# 3_bootleg-alps-mcu.net
KiCad netlist of a schematic drawn in Altium Designer
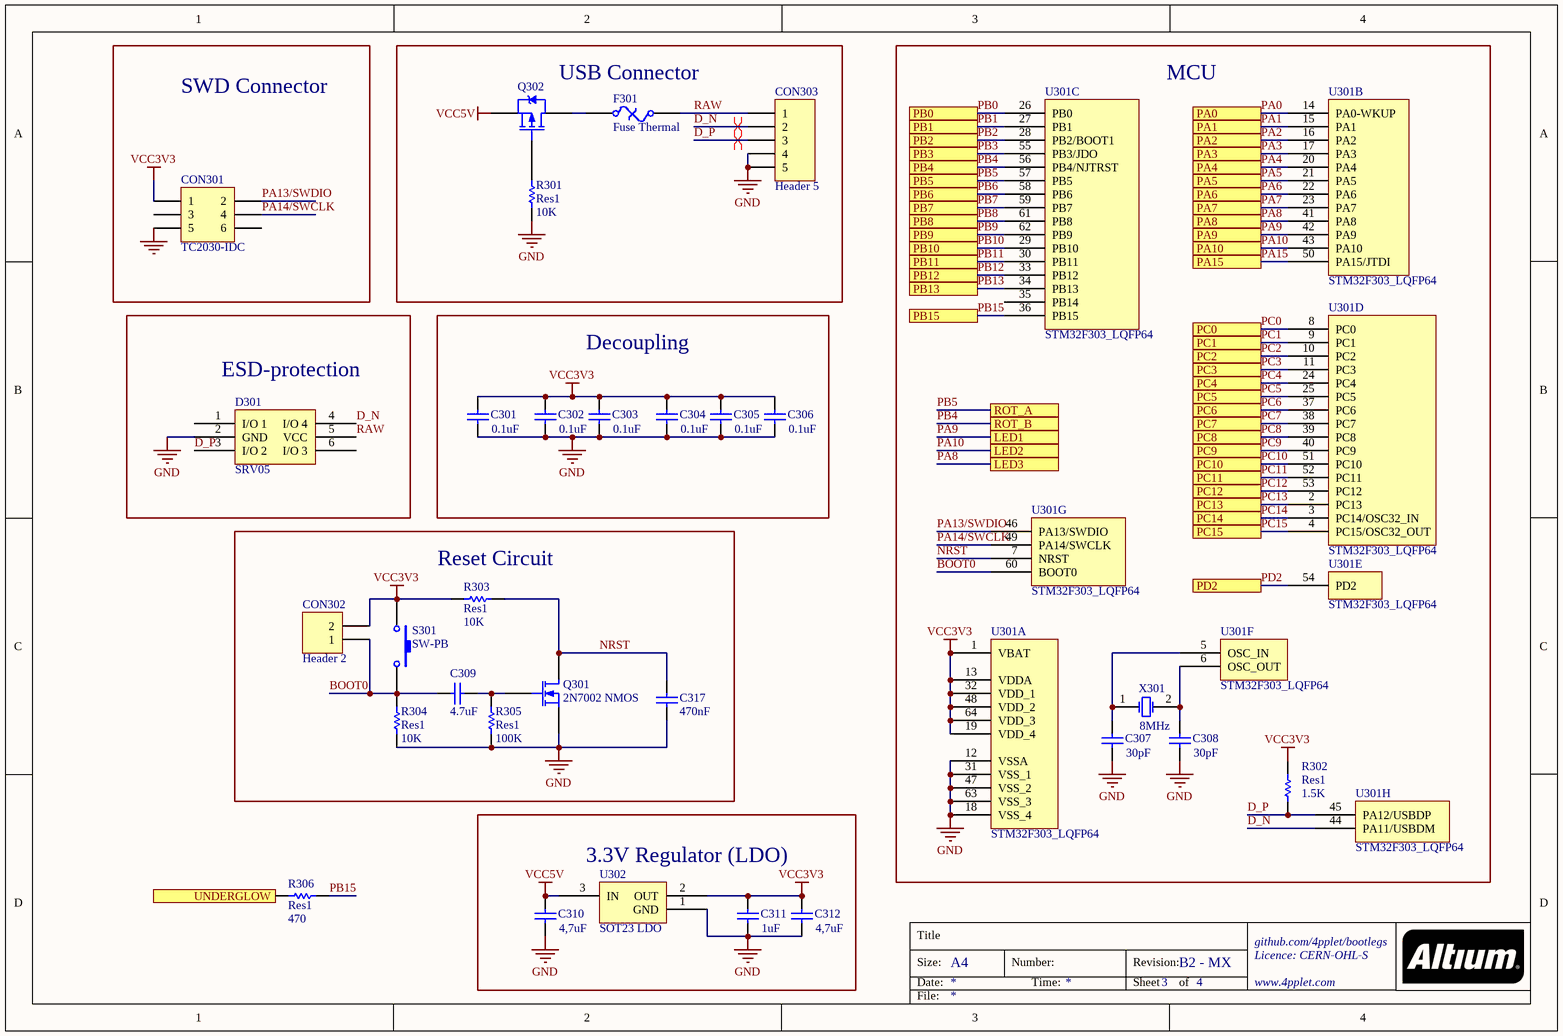
[diagram p0: 3_bootleg-alps-mcu.SchDoc]

(export (version "E")
  (design (tool "Eeschema 10.0.6"))
  (components
    (comp (ref "C301")
      (value "0.1uF")
      (footprint "C0603[1608]")
      (description "Capacitor")
      (fields (field (name "MFG") "KEMET") (field (name "LCSC PART #") "C14663"))
      (libsource (lib "Miscellaneous Devices") (part "Cap"))
    )
    (comp (ref "C302")
      (value "0.1uF")
      (footprint "C0603[1608]")
      (description "Capacitor")
      (fields (field (name "MFG") "KEMET") (field (name "LCSC PART #") "C14663"))
      (libsource (lib "Miscellaneous Devices") (part "Cap"))
    )
    (comp (ref "C303")
      (value "0.1uF")
      (footprint "C0603[1608]")
      (description "Capacitor")
      (fields (field (name "MFG") "KEMET") (field (name "LCSC PART #") "C14663"))
      (libsource (lib "Miscellaneous Devices") (part "Cap"))
    )
    (comp (ref "C304")
      (value "0.1uF")
      (footprint "C0603[1608]")
      (description "Capacitor")
      (fields (field (name "MFG") "KEMET") (field (name "LCSC PART #") "C14663"))
      (libsource (lib "Miscellaneous Devices") (part "Cap"))
    )
    (comp (ref "C305")
      (value "0.1uF")
      (footprint "C0603[1608]")
      (description "Capacitor")
      (fields (field (name "MFG") "KEMET") (field (name "LCSC PART #") "C14663"))
      (libsource (lib "Miscellaneous Devices") (part "Cap"))
    )
    (comp (ref "C306")
      (value "0.1uF")
      (footprint "C0603[1608]")
      (description "Capacitor")
      (fields (field (name "MFG") "KEMET") (field (name "LCSC PART #") "C14663"))
      (libsource (lib "Miscellaneous Devices") (part "Cap"))
    )
    (comp (ref "C307")
      (value "30pF")
      (footprint "C0603[1608]")
      (description "Capacitor")
      (fields (field (name "LCSC PART #") "C22397") (field (name "MRF.PART") "CL10C300JB8NNNC"))
      (libsource (lib "Miscellaneous Devices") (part "Cap"))
    )
    (comp (ref "C308")
      (value "30pF")
      (footprint "C0603[1608]")
      (description "Capacitor")
      (fields (field (name "LCSC PART #") "C22397") (field (name "MRF.PART") "CL10C300JB8NNNC"))
      (libsource (lib "Miscellaneous Devices") (part "Cap"))
    )
    (comp (ref "C309")
      (value "4.7uF")
      (footprint "C0603[1608]")
      (description "Capacitor")
      (fields (field (name "LCSC PART #") "C19666"))
      (libsource (lib "Miscellaneous Devices") (part "Cap"))
    )
    (comp (ref "C310")
      (value "4,7uF")
      (footprint "C0603[1608]")
      (description "Capacitor")
      (fields (field (name "LCSC PART #") "C19666"))
      (libsource (lib "Miscellaneous Devices") (part "Cap"))
    )
    (comp (ref "C311")
      (value "1uF")
      (footprint "C0603[1608]")
      (description "Capacitor")
      (fields (field (name "MFG") "KEMET") (field (name "LCSC PART #") "C15849"))
      (libsource (lib "Miscellaneous Devices") (part "Cap"))
    )
    (comp (ref "C312")
      (value "4,7uF")
      (footprint "C0603[1608]")
      (description "Capacitor")
      (fields (field (name "LCSC PART #") "C19666"))
      (libsource (lib "Miscellaneous Devices") (part "Cap"))
    )
    (comp (ref "C317")
      (value "470nF")
      (footprint "C0603[1608]")
      (description "Capacitor")
      (fields (field (name "MFG") "KEMET") (field (name "LCSC PART #") "C14663"))
      (libsource (lib "Miscellaneous Devices") (part "Cap"))
    )
    (comp (ref "CON301")
      (value "TC2030-IDC")
      (footprint "TC2030-IDC-NL")
      (description "Header, 3-Pin, Dual row")
      (libsource (lib "Miscellaneous Connectors") (part "Header 3X2"))
    )
    (comp (ref "CON302")
      (value "Header 2")
      (footprint "HDR1X2")
      (description "Header, 2-Pin")
      (libsource (lib "Miscellaneous Connectors") (part "Header 2"))
    )
    (comp (ref "CON303")
      (value "Header 5")
      (footprint "JST SM04B-SRSS-TB")
      (description "JST for USB daughter board")
      (fields (field (name "MFG") "JST Sales America Inc.") (field (name "LCSC PART #") "C160404"))
      (libsource (lib "Miscellaneous Connectors") (part "Header 5"))
    )
    (comp (ref "D301")
      (value "SRV05")
      (footprint "SOT-23-6")
      (fields (field (name "LCSC PART #") "C85364") (field (name "MRF.PART") "SRV05-4-P-T7"))
      (libsource (lib "Keebs") (part "SRV05"))
    )
    (comp (ref "F301")
      (value "Fuse Thermal")
      (footprint "C1206[3216]")
      (description "Thermal Fuse")
      (fields (field (name "MFG") "Bel Fuse Inc.") (field (name "LCSC PART #") "C135338"))
      (libsource (lib "Miscellaneous Devices") (part "Fuse Thermal"))
    )
    (comp (ref "Q301")
      (value "2N7002 NMOS")
      (footprint "SOT-23-3")
      (description "N-Channel MOSFET")
      (fields (field (name "LCSC PART #") "C8545") (field (name "MRF.PART") "2N7002"))
      (libsource (lib "Miscellaneous Devices") (part "MOSFET-N"))
    )
    (comp (ref "Q302")
      (value "PMOS-2")
      (footprint "SOT-23-3")
      (description "P-Channel Power MOSFET")
      (fields (field (name "LCSC PART #") "C10487") (field (name "MRF.PART") "SI2301CDS-T1-GE3"))
      (libsource (lib "Miscellaneous Devices") (part "PMOS-2"))
    )
    (comp (ref "R301")
      (value "Res1")
      (footprint "R0603[1608]")
      (description "Resistor")
      (fields
        (field (name "ALTIUM_VALUE") "10K")
        (field (name "MFG") "Panasonic Electronic Components")
        (field (name "LCSC PART #") "C25804")
      )
      (libsource (lib "Miscellaneous Devices") (part "Res1"))
    )
    (comp (ref "R302")
      (value "Res1")
      (footprint "R0603[1608]")
      (description "Resistor")
      (fields
        (field (name "ALTIUM_VALUE") "1.5K")
        (field (name "LCSC PART #") "C22843")
        (field (name "MRF.PART") "0603WAF1501T5E")
      )
      (libsource (lib "Miscellaneous Devices") (part "Res1"))
    )
    (comp (ref "R303")
      (value "Res1")
      (footprint "R0603[1608]")
      (description "Resistor")
      (fields
        (field (name "ALTIUM_VALUE") "10K")
        (field (name "MFG") "Panasonic Electronic Components")
        (field (name "LCSC PART #") "C25804")
      )
      (libsource (lib "Miscellaneous Devices") (part "Res1"))
    )
    (comp (ref "R304")
      (value "Res1")
      (footprint "R0603[1608]")
      (description "Resistor")
      (fields
        (field (name "ALTIUM_VALUE") "10K")
        (field (name "MFG") "Panasonic Electronic Components")
        (field (name "LCSC PART #") "C25804")
      )
      (libsource (lib "Miscellaneous Devices") (part "Res1"))
    )
    (comp (ref "R305")
      (value "Res1")
      (footprint "R0603[1608]")
      (description "Resistor")
      (fields
        (field (name "ALTIUM_VALUE") "100K")
        (field (name "LCSC PART #") "C25803")
        (field (name "MRF.PART") "0603WAF1003T5E")
      )
      (libsource (lib "Miscellaneous Devices") (part "Res1"))
    )
    (comp (ref "R306")
      (value "Res1")
      (footprint "R0603[1608]")
      (description "Resistor")
      (fields
        (field (name "ALTIUM_VALUE") "470")
        (field (name "MFG") "Panasonic Electronic Components")
        (field (name "LCSC PART #") "C23179")
      )
      (libsource (lib "Miscellaneous Devices") (part "Res1"))
    )
    (comp (ref "S301")
      (value "SW-PB")
      (footprint "XKB Switch")
      (description "Switch")
      (fields (field (name "MFG") "C&K") (field (name "MRF.PART") "TS-1187A-C-D-B"))
      (libsource (lib "Miscellaneous Devices") (part "SW-PB"))
    )
    (comp (ref "U301")
      (value "STM32F303_LQFP64")
      (footprint "STM32 - LQFP64, 10x10mm")
      (fields (field (name "LCSC PART #") "C183214") (field (name "MRF.PART") "STM32F303RET6"))
      (libsource (lib "Keebs") (part "STM32F303_LQFP64"))
    )
    (comp (ref "U302")
      (value "SOT23 LDO")
      (footprint "SOT-23-3")
      (fields
        (field (name "LCSC PART #") "C5446")
        (field (name "MRF.PART") "XC6206P332MR")
        (field (name "MFG") "Texas Instruments")
      )
      (libsource (lib "Keebs") (part "SOT23 LDO"))
    )
    (comp (ref "X301")
      (value "8MHz")
      (footprint "CTS 445-series crystal")
      (description "Crystal Oscillator")
      (fields (field (name "LCSC PART #") "C115962") (field (name "MRF.PART") "X50328MSB2GI"))
      (libsource (lib "Miscellaneous Devices") (part "XTAL"))
    )
  )
  (nets
    (net (code "1") (name "/BOOT0") (class "Default")
      (node (ref "C309") (pin "1") (pinfunction "1_1") (pintype "passive"))
      (node (ref "CON302") (pin "1") (pinfunction "1_1") (pintype "passive"))
      (node (ref "R304") (pin "1") (pinfunction "1_1") (pintype "passive"))
      (node (ref "S301") (pin "2") (pinfunction "2_2") (pintype "passive"))
      (node (ref "U301") (pin "60") (pinfunction "BOOT0_60") (pintype "passive"))
    )
    (net (code "2") (name "/D_N") (class "Default")
      (node (ref "CON303") (pin "2") (pinfunction "2_2") (pintype "passive"))
      (node (ref "D301") (pin "4") (pinfunction "I/O_4_4") (pintype "passive"))
      (node (ref "U301") (pin "44") (pinfunction "PA11/USBDM_44") (pintype "passive"))
    )
    (net (code "3") (name "/D_P") (class "Default")
      (node (ref "CON303") (pin "3") (pinfunction "3_3") (pintype "passive"))
      (node (ref "D301") (pin "3") (pinfunction "I/O_2_3") (pintype "passive"))
      (node (ref "R302") (pin "2") (pinfunction "2_2") (pintype "passive"))
      (node (ref "U301") (pin "45") (pinfunction "PA12/USBDP_45") (pintype "passive"))
    )
    (net (code "4") (name "/NRST") (class "Default")
      (node (ref "C317") (pin "1") (pinfunction "1_1") (pintype "passive"))
      (node (ref "Q301") (pin "3") (pinfunction "D_3") (pintype "passive"))
      (node (ref "R303") (pin "2") (pinfunction "2_2") (pintype "passive"))
      (node (ref "U301") (pin "7") (pinfunction "NRST_7") (pintype "passive"))
    )
    (net (code "5") (name "/PA0") (class "Default")
      (node (ref "U301") (pin "14") (pinfunction "PA0-WKUP_14") (pintype "passive"))
    )
    (net (code "6") (name "/PA1") (class "Default")
      (node (ref "U301") (pin "15") (pinfunction "PA1_15") (pintype "passive"))
    )
    (net (code "7") (name "/PA2") (class "Default")
      (node (ref "U301") (pin "16") (pinfunction "PA2_16") (pintype "passive"))
    )
    (net (code "8") (name "/PA3") (class "Default")
      (node (ref "U301") (pin "17") (pinfunction "PA3_17") (pintype "passive"))
    )
    (net (code "9") (name "/PA4") (class "Default")
      (node (ref "U301") (pin "20") (pinfunction "PA4_20") (pintype "passive"))
    )
    (net (code "10") (name "/PA5") (class "Default")
      (node (ref "U301") (pin "21") (pinfunction "PA5_21") (pintype "passive"))
    )
    (net (code "11") (name "/PA6") (class "Default")
      (node (ref "U301") (pin "22") (pinfunction "PA6_22") (pintype "passive"))
    )
    (net (code "12") (name "/PA7") (class "Default")
      (node (ref "U301") (pin "23") (pinfunction "PA7_23") (pintype "passive"))
    )
    (net (code "13") (name "/PA8") (class "Default")
      (node (ref "U301") (pin "41") (pinfunction "PA8_41") (pintype "passive"))
    )
    (net (code "14") (name "/PA9") (class "Default")
      (node (ref "U301") (pin "42") (pinfunction "PA9_42") (pintype "passive"))
    )
    (net (code "15") (name "/PA10") (class "Default")
      (node (ref "U301") (pin "43") (pinfunction "PA10_43") (pintype "passive"))
    )
    (net (code "16") (name "/PA13{slash}SWDIO") (class "Default")
      (node (ref "CON301") (pin "2") (pinfunction "2_2") (pintype "passive"))
      (node (ref "U301") (pin "46") (pinfunction "PA13/SWDIO_46") (pintype "passive"))
    )
    (net (code "17") (name "/PA14{slash}SWCLK") (class "Default")
      (node (ref "CON301") (pin "4") (pinfunction "4_4") (pintype "passive"))
      (node (ref "U301") (pin "49") (pinfunction "PA14/SWCLK_49") (pintype "passive"))
    )
    (net (code "18") (name "/PA15") (class "Default")
      (node (ref "U301") (pin "50") (pinfunction "PA15/JTDI_50") (pintype "passive"))
    )
    (net (code "19") (name "/PB0") (class "Default")
      (node (ref "U301") (pin "26") (pinfunction "PB0_26") (pintype "passive"))
    )
    (net (code "20") (name "/PB1") (class "Default")
      (node (ref "U301") (pin "27") (pinfunction "PB1_27") (pintype "passive"))
    )
    (net (code "21") (name "/PB2") (class "Default")
      (node (ref "U301") (pin "28") (pinfunction "PB2/BOOT1_28") (pintype "passive"))
    )
    (net (code "22") (name "/PB3") (class "Default")
      (node (ref "U301") (pin "55") (pinfunction "PB3/JDO_55") (pintype "passive"))
    )
    (net (code "23") (name "/PB4") (class "Default")
      (node (ref "U301") (pin "56") (pinfunction "PB4/NJTRST_56") (pintype "passive"))
    )
    (net (code "24") (name "/PB5") (class "Default")
      (node (ref "U301") (pin "57") (pinfunction "PB5_57") (pintype "passive"))
    )
    (net (code "25") (name "/PB6") (class "Default")
      (node (ref "U301") (pin "58") (pinfunction "PB6_58") (pintype "passive"))
    )
    (net (code "26") (name "/PB7") (class "Default")
      (node (ref "U301") (pin "59") (pinfunction "PB7_59") (pintype "passive"))
    )
    (net (code "27") (name "/PB8") (class "Default")
      (node (ref "U301") (pin "61") (pinfunction "PB8_61") (pintype "passive"))
    )
    (net (code "28") (name "/PB9") (class "Default")
      (node (ref "U301") (pin "62") (pinfunction "PB9_62") (pintype "passive"))
    )
    (net (code "29") (name "/PB10") (class "Default")
      (node (ref "U301") (pin "29") (pinfunction "PB10_29") (pintype "passive"))
    )
    (net (code "30") (name "/PB11") (class "Default")
      (node (ref "U301") (pin "30") (pinfunction "PB11_30") (pintype "passive"))
    )
    (net (code "31") (name "/PB12") (class "Default")
      (node (ref "U301") (pin "33") (pinfunction "PB12_33") (pintype "passive"))
    )
    (net (code "32") (name "/PB13") (class "Default")
      (node (ref "U301") (pin "34") (pinfunction "PB13_34") (pintype "passive"))
    )
    (net (code "33") (name "/PB15") (class "Default")
      (node (ref "R306") (pin "2") (pinfunction "2_2") (pintype "passive"))
      (node (ref "U301") (pin "36") (pinfunction "PB15_36") (pintype "passive"))
    )
    (net (code "34") (name "/PC0") (class "Default")
      (node (ref "U301") (pin "8") (pinfunction "PC0_8") (pintype "passive"))
    )
    (net (code "35") (name "/PC1") (class "Default")
      (node (ref "U301") (pin "9") (pinfunction "PC1_9") (pintype "passive"))
    )
    (net (code "36") (name "/PC2") (class "Default")
      (node (ref "U301") (pin "10") (pinfunction "PC2_10") (pintype "passive"))
    )
    (net (code "37") (name "/PC3") (class "Default")
      (node (ref "U301") (pin "11") (pinfunction "PC3_11") (pintype "passive"))
    )
    (net (code "38") (name "/PC4") (class "Default")
      (node (ref "U301") (pin "24") (pinfunction "PC4_24") (pintype "passive"))
    )
    (net (code "39") (name "/PC5") (class "Default")
      (node (ref "U301") (pin "25") (pinfunction "PC5_25") (pintype "passive"))
    )
    (net (code "40") (name "/PC6") (class "Default")
      (node (ref "U301") (pin "37") (pinfunction "PC6_37") (pintype "passive"))
    )
    (net (code "41") (name "/PC7") (class "Default")
      (node (ref "U301") (pin "38") (pinfunction "PC7_38") (pintype "passive"))
    )
    (net (code "42") (name "/PC8") (class "Default")
      (node (ref "U301") (pin "39") (pinfunction "PC8_39") (pintype "passive"))
    )
    (net (code "43") (name "/PC9") (class "Default")
      (node (ref "U301") (pin "40") (pinfunction "PC9_40") (pintype "passive"))
    )
    (net (code "44") (name "/PC10") (class "Default")
      (node (ref "U301") (pin "51") (pinfunction "PC10_51") (pintype "passive"))
    )
    (net (code "45") (name "/PC11") (class "Default")
      (node (ref "U301") (pin "52") (pinfunction "PC11_52") (pintype "passive"))
    )
    (net (code "46") (name "/PC12") (class "Default")
      (node (ref "U301") (pin "53") (pinfunction "PC12_53") (pintype "passive"))
    )
    (net (code "47") (name "/PC13") (class "Default")
      (node (ref "U301") (pin "2") (pinfunction "PC13_2") (pintype "passive"))
    )
    (net (code "48") (name "/PC14") (class "Default")
      (node (ref "U301") (pin "3") (pinfunction "PC14/OSC32_IN_3") (pintype "passive"))
    )
    (net (code "49") (name "/PC15") (class "Default")
      (node (ref "U301") (pin "4") (pinfunction "PC15/OSC32_OUT_4") (pintype "passive"))
    )
    (net (code "50") (name "/PD2") (class "Default")
      (node (ref "U301") (pin "54") (pinfunction "PD2_54") (pintype "passive"))
    )
    (net (code "51") (name "/RAW") (class "Default")
      (node (ref "CON303") (pin "1") (pinfunction "1_1") (pintype "passive"))
      (node (ref "D301") (pin "5") (pinfunction "VCC_5") (pintype "passive"))
      (node (ref "F301") (pin "2") (pinfunction "2_2") (pintype "passive"))
    )
    (net (code "52") (name "/UNDERGLOW") (class "Default")
      (node (ref "R306") (pin "1") (pinfunction "1_1") (pintype "passive"))
    )
    (net (code "53") (name "GND") (class "Default")
      (node (ref "C301") (pin "1") (pinfunction "1_1") (pintype "passive"))
      (node (ref "C302") (pin "1") (pinfunction "1_1") (pintype "passive"))
      (node (ref "C303") (pin "1") (pinfunction "1_1") (pintype "passive"))
      (node (ref "C304") (pin "1") (pinfunction "1_1") (pintype "passive"))
      (node (ref "C305") (pin "1") (pinfunction "1_1") (pintype "passive"))
      (node (ref "C306") (pin "1") (pinfunction "1_1") (pintype "passive"))
      (node (ref "C307") (pin "1") (pinfunction "1_1") (pintype "passive"))
      (node (ref "C308") (pin "1") (pinfunction "1_1") (pintype "passive"))
      (node (ref "C310") (pin "1") (pinfunction "1_1") (pintype "passive"))
      (node (ref "C311") (pin "1") (pinfunction "1_1") (pintype "passive"))
      (node (ref "C312") (pin "1") (pinfunction "1_1") (pintype "passive"))
      (node (ref "C317") (pin "2") (pinfunction "2_2") (pintype "passive"))
      (node (ref "CON301") (pin "5") (pinfunction "5_5") (pintype "passive"))
      (node (ref "CON303") (pin "4") (pinfunction "4_4") (pintype "passive"))
      (node (ref "CON303") (pin "5") (pinfunction "5_5") (pintype "passive"))
      (node (ref "D301") (pin "2") (pinfunction "GND_2") (pintype "passive"))
      (node (ref "Q301") (pin "2") (pinfunction "S_2") (pintype "passive"))
      (node (ref "R301") (pin "2") (pinfunction "2_2") (pintype "passive"))
      (node (ref "R304") (pin "2") (pinfunction "2_2") (pintype "passive"))
      (node (ref "R305") (pin "2") (pinfunction "2_2") (pintype "passive"))
      (node (ref "U301") (pin "12") (pinfunction "VSSA_12") (pintype "passive"))
      (node (ref "U301") (pin "18") (pinfunction "VSS_4_18") (pintype "passive"))
      (node (ref "U301") (pin "31") (pinfunction "VSS_1_31") (pintype "passive"))
      (node (ref "U301") (pin "47") (pinfunction "VSS_2_47") (pintype "passive"))
      (node (ref "U301") (pin "63") (pinfunction "VSS_3_63") (pintype "passive"))
      (node (ref "U302") (pin "1") (pinfunction "GND_1") (pintype "passive"))
    )
    (net (code "54") (name "Net-(Q301-G)") (class "Default")
      (node (ref "C309") (pin "2") (pinfunction "2_2") (pintype "passive"))
      (node (ref "Q301") (pin "1") (pinfunction "G_1") (pintype "passive"))
      (node (ref "R305") (pin "1") (pinfunction "1_1") (pintype "passive"))
    )
    (net (code "55") (name "Net-(Q302-D)") (class "Default")
      (node (ref "F301") (pin "1") (pinfunction "1_1") (pintype "passive"))
      (node (ref "Q302") (pin "3") (pinfunction "D_3") (pintype "passive"))
    )
    (net (code "56") (name "Net-(Q302-G)") (class "Default")
      (node (ref "Q302") (pin "1") (pinfunction "G_1") (pintype "passive"))
      (node (ref "R301") (pin "1") (pinfunction "1_1") (pintype "passive"))
    )
    (net (code "57") (name "Net-(U301F-OSC_IN)") (class "Default")
      (node (ref "C307") (pin "2") (pinfunction "2_2") (pintype "passive"))
      (node (ref "U301") (pin "5") (pinfunction "OSC_IN_5") (pintype "passive"))
      (node (ref "X301") (pin "1") (pinfunction "OSC1_1") (pintype "passive"))
    )
    (net (code "58") (name "Net-(U301F-OSC_OUT)") (class "Default")
      (node (ref "C308") (pin "2") (pinfunction "2_2") (pintype "passive"))
      (node (ref "U301") (pin "6") (pinfunction "OSC_OUT_6") (pintype "passive"))
      (node (ref "X301") (pin "2") (pinfunction "OSC2_2") (pintype "passive"))
    )
    (net (code "59") (name "VCC3V3") (class "Default")
      (node (ref "C301") (pin "2") (pinfunction "2_2") (pintype "passive"))
      (node (ref "C302") (pin "2") (pinfunction "2_2") (pintype "passive"))
      (node (ref "C303") (pin "2") (pinfunction "2_2") (pintype "passive"))
      (node (ref "C304") (pin "2") (pinfunction "2_2") (pintype "passive"))
      (node (ref "C305") (pin "2") (pinfunction "2_2") (pintype "passive"))
      (node (ref "C306") (pin "2") (pinfunction "2_2") (pintype "passive"))
      (node (ref "C311") (pin "2") (pinfunction "2_2") (pintype "passive"))
      (node (ref "C312") (pin "2") (pinfunction "2_2") (pintype "passive"))
      (node (ref "CON301") (pin "1") (pinfunction "1_1") (pintype "passive"))
      (node (ref "CON302") (pin "2") (pinfunction "2_2") (pintype "passive"))
      (node (ref "R302") (pin "1") (pinfunction "1_1") (pintype "passive"))
      (node (ref "R303") (pin "1") (pinfunction "1_1") (pintype "passive"))
      (node (ref "S301") (pin "1") (pinfunction "1_1") (pintype "passive"))
      (node (ref "U301") (pin "1") (pinfunction "VBAT_1") (pintype "passive"))
      (node (ref "U301") (pin "13") (pinfunction "VDDA_13") (pintype "passive"))
      (node (ref "U301") (pin "19") (pinfunction "VDD_4_19") (pintype "passive"))
      (node (ref "U301") (pin "32") (pinfunction "VDD_1_32") (pintype "passive"))
      (node (ref "U301") (pin "48") (pinfunction "VDD_2_48") (pintype "passive"))
      (node (ref "U301") (pin "64") (pinfunction "VDD_3_64") (pintype "passive"))
      (node (ref "U302") (pin "2") (pinfunction "OUT_2") (pintype "passive"))
    )
    (net (code "60") (name "VCC5V") (class "Default")
      (node (ref "C310") (pin "2") (pinfunction "2_2") (pintype "passive"))
      (node (ref "Q302") (pin "2") (pinfunction "S_2") (pintype "passive"))
      (node (ref "U302") (pin "3") (pinfunction "IN_3") (pintype "passive"))
    )
    (net (code "61") (name "unconnected-(CON301-Pad3)") (class "Default")
      (node (ref "CON301") (pin "3") (pinfunction "3_3") (pintype "passive"))
    )
    (net (code "62") (name "unconnected-(CON301-Pad6)") (class "Default")
      (node (ref "CON301") (pin "6") (pinfunction "6_6") (pintype "passive"))
    )
    (net (code "63") (name "unconnected-(D301-I{slash}O_1-Pad1)") (class "Default")
      (node (ref "D301") (pin "1") (pinfunction "I/O_1_1") (pintype "passive"))
    )
    (net (code "64") (name "unconnected-(D301-I{slash}O_3-Pad6)") (class "Default")
      (node (ref "D301") (pin "6") (pinfunction "I/O_3_6") (pintype "passive"))
    )
    (net (code "65") (name "unconnected-(U301C-PB14-Pad35)") (class "Default")
      (node (ref "U301") (pin "35") (pinfunction "PB14_35") (pintype "passive"))
    )
  )
)
